# KNX_Relay_16CH_V0_2.net
KiCad netlist of a schematic drawn in Altium Designer
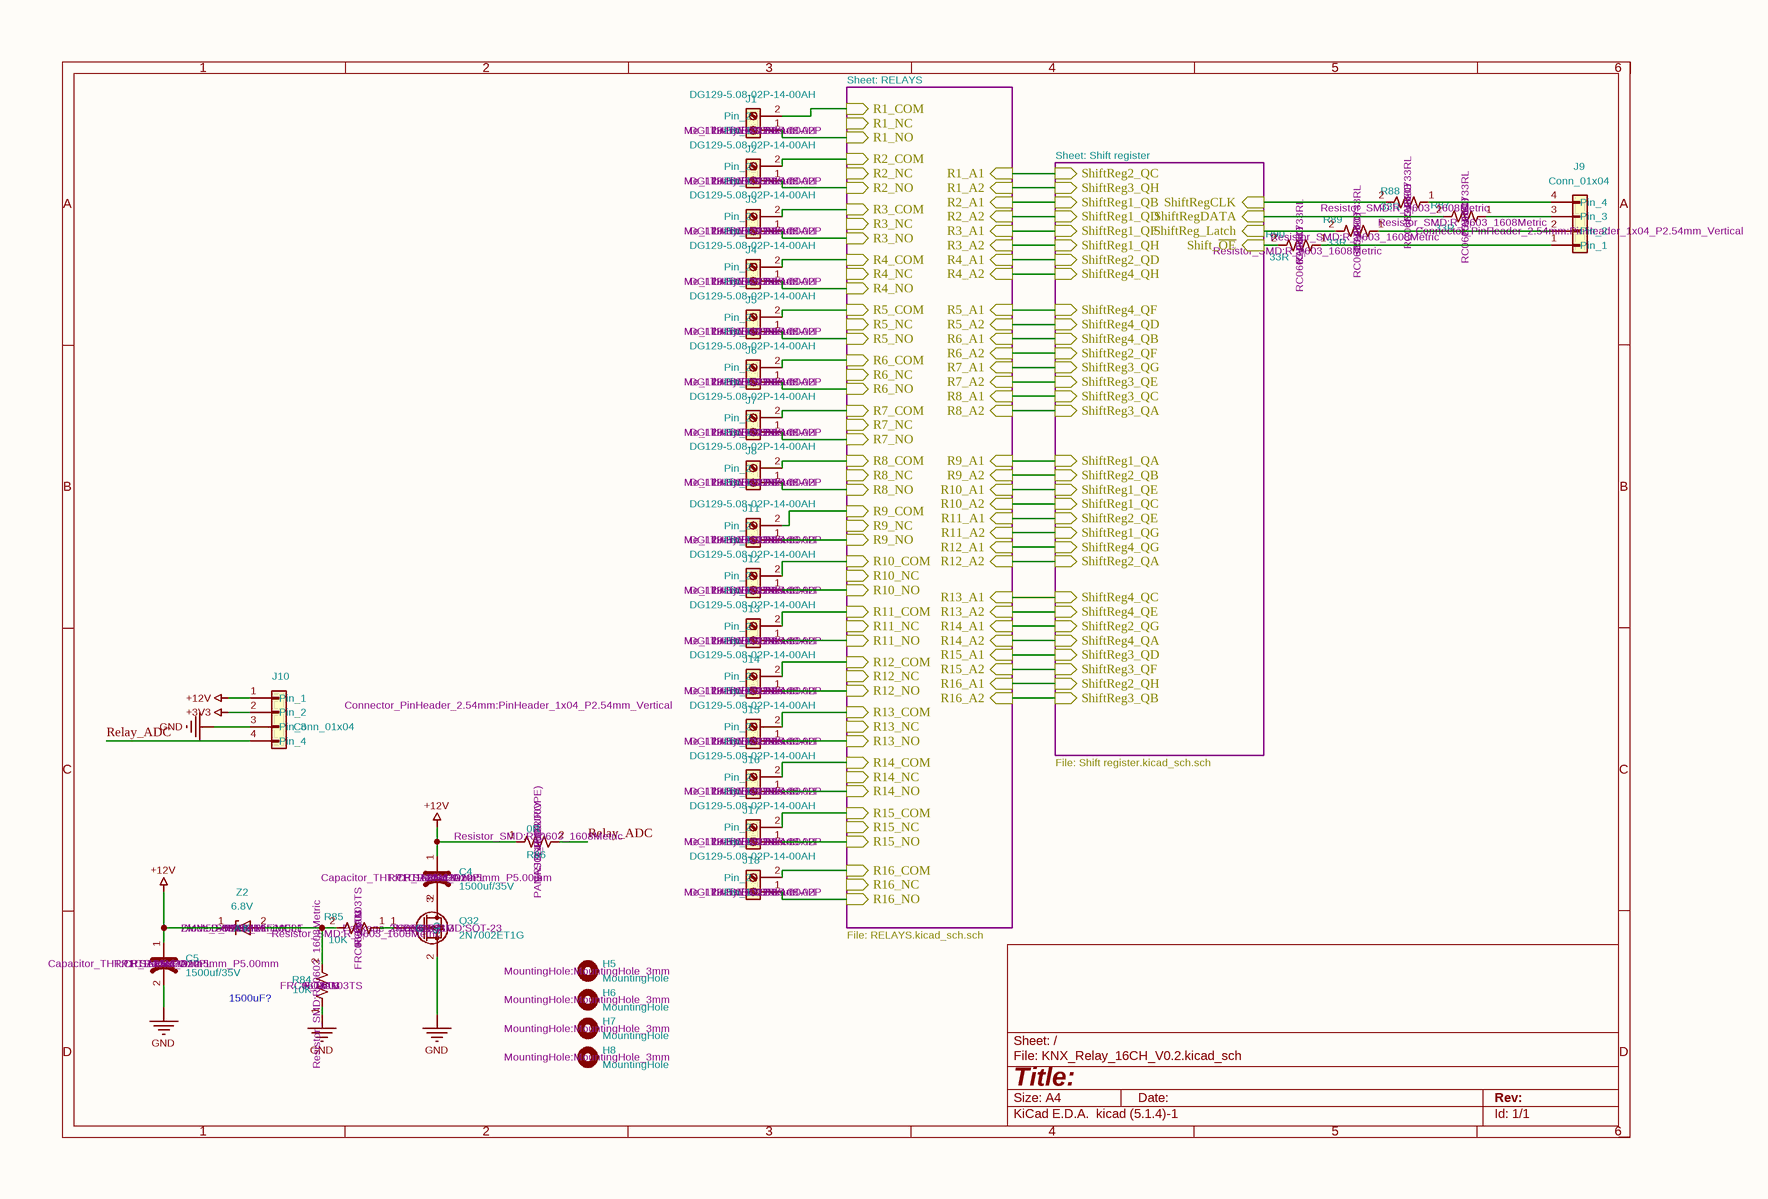
[diagram p0: KNX_Relay_16CH_V0.2.SchDoc]

(export (version "E")
  (design (tool "Eeschema 10.0.6"))
  (components
    (comp (ref "C4")
      (value "1500uf/35V")
      (footprint "Capacitor_THT:CP_Radial_D12.5mm_P5.00mm")
      (fields
        (field (name "MANUFACTURER PART NUMBER") "RP1C158M12020PL")
        (field (name "MANUFACTURER") "SAMWHA")
        (field (name "PACKAGE") "THT 12.5x20mm")
      )
      (libsource (lib "Device") (part "C_US"))
    )
    (comp (ref "C5")
      (value "1500uf/35V")
      (footprint "Capacitor_THT:CP_Radial_D12.5mm_P5.00mm")
      (fields
        (field (name "MANUFACTURER PART NUMBER") "RP1C158M12020PL")
        (field (name "MANUFACTURER") "SAMWHA")
        (field (name "PACKAGE") "THT 12.5x20mm")
      )
      (libsource (lib "Device") (part "C_US"))
    )
    (comp (ref "H5")
      (value "MountingHole")
      (footprint "MountingHole:MountingHole_3mm")
      (libsource (lib "Mechanical") (part "MountingHole"))
    )
    (comp (ref "H6")
      (value "MountingHole")
      (footprint "MountingHole:MountingHole_3mm")
      (libsource (lib "Mechanical") (part "MountingHole"))
    )
    (comp (ref "H7")
      (value "MountingHole")
      (footprint "MountingHole:MountingHole_3mm")
      (libsource (lib "Mechanical") (part "MountingHole"))
    )
    (comp (ref "H8")
      (value "MountingHole")
      (footprint "MountingHole:MountingHole_3mm")
      (libsource (lib "Mechanical") (part "MountingHole"))
    )
    (comp (ref "J1")
      (value "DG129-5.08-02P-14-00AH")
      (footprint "Me_Library:DG129-5.08-02P")
      (fields
        (field (name "MANUFACTURER PART NUMBER") "DG129-5.08-02P-14-00AH")
        (field (name "MANUFACTURER") "DEGSON")
        (field (name "PACKAGE") "THT V/T  5.08mm")
      )
      (libsource (lib "Connector") (part "Screw_Terminal_01x02"))
    )
    (comp (ref "J2")
      (value "DG129-5.08-02P-14-00AH")
      (footprint "Me_Library:DG129-5.08-02P")
      (fields
        (field (name "MANUFACTURER PART NUMBER") "DG129-5.08-02P-14-00AH")
        (field (name "MANUFACTURER") "DEGSON")
        (field (name "PACKAGE") "THT V/T  5.08mm")
      )
      (libsource (lib "Connector") (part "Screw_Terminal_01x02"))
    )
    (comp (ref "J3")
      (value "DG129-5.08-02P-14-00AH")
      (footprint "Me_Library:DG129-5.08-02P")
      (fields
        (field (name "MANUFACTURER PART NUMBER") "DG129-5.08-02P-14-00AH")
        (field (name "MANUFACTURER") "DEGSON")
        (field (name "PACKAGE") "THT V/T  5.08mm")
      )
      (libsource (lib "Connector") (part "Screw_Terminal_01x02"))
    )
    (comp (ref "J4")
      (value "DG129-5.08-02P-14-00AH")
      (footprint "Me_Library:DG129-5.08-02P")
      (fields
        (field (name "MANUFACTURER PART NUMBER") "DG129-5.08-02P-14-00AH")
        (field (name "MANUFACTURER") "DEGSON")
        (field (name "PACKAGE") "THT V/T  5.08mm")
      )
      (libsource (lib "Connector") (part "Screw_Terminal_01x02"))
    )
    (comp (ref "J5")
      (value "DG129-5.08-02P-14-00AH")
      (footprint "Me_Library:DG129-5.08-02P")
      (fields
        (field (name "MANUFACTURER PART NUMBER") "DG129-5.08-02P-14-00AH")
        (field (name "MANUFACTURER") "DEGSON")
        (field (name "PACKAGE") "THT V/T  5.08mm")
      )
      (libsource (lib "Connector") (part "Screw_Terminal_01x02"))
    )
    (comp (ref "J6")
      (value "DG129-5.08-02P-14-00AH")
      (footprint "Me_Library:DG129-5.08-02P")
      (fields
        (field (name "MANUFACTURER PART NUMBER") "DG129-5.08-02P-14-00AH")
        (field (name "MANUFACTURER") "DEGSON")
        (field (name "PACKAGE") "THT V/T  5.08mm")
      )
      (libsource (lib "Connector") (part "Screw_Terminal_01x02"))
    )
    (comp (ref "J7")
      (value "DG129-5.08-02P-14-00AH")
      (footprint "Me_Library:DG129-5.08-02P")
      (fields
        (field (name "MANUFACTURER PART NUMBER") "DG129-5.08-02P-14-00AH")
        (field (name "MANUFACTURER") "DEGSON")
        (field (name "PACKAGE") "THT V/T  5.08mm")
      )
      (libsource (lib "Connector") (part "Screw_Terminal_01x02"))
    )
    (comp (ref "J8")
      (value "DG129-5.08-02P-14-00AH")
      (footprint "Me_Library:DG129-5.08-02P")
      (fields
        (field (name "MANUFACTURER PART NUMBER") "DG129-5.08-02P-14-00AH")
        (field (name "MANUFACTURER") "DEGSON")
        (field (name "PACKAGE") "THT V/T  5.08mm")
      )
      (libsource (lib "Connector") (part "Screw_Terminal_01x02"))
    )
    (comp (ref "J9")
      (value "Conn_01x04")
      (footprint "Connector_PinHeader_2.54mm:PinHeader_1x04_P2.54mm_Vertical")
      (description "FEMALE HEADER 4PIN(1x4) 2.54mm THT V/T TRAY")
      (fields
        (field (name "MANUFACTURER PART NUMBER") "5PS1SDA85-104G0NNNAL-00")
        (field (name "MANUFACTURER") "AMTEK")
      )
      (libsource (lib "Connector_Generic") (part "Conn_01x04"))
    )
    (comp (ref "J10")
      (value "Conn_01x04")
      (footprint "Connector_PinHeader_2.54mm:PinHeader_1x04_P2.54mm_Vertical")
      (description "FEMALE HEADER 4PIN(1x4) 2.54mm THT V/T TRAY")
      (fields
        (field (name "MANUFACTURER PART NUMBER") "5PS1SDA85-104G0NNNAL-00")
        (field (name "MANUFACTURER") "AMTEK")
      )
      (libsource (lib "") (part "Conn_01x04_1"))
    )
    (comp (ref "J11")
      (value "DG129-5.08-02P-14-00AH")
      (footprint "Me_Library:DG129-5.08-02P")
      (fields
        (field (name "MANUFACTURER PART NUMBER") "DG129-5.08-02P-14-00AH")
        (field (name "MANUFACTURER") "DEGSON")
        (field (name "PACKAGE") "THT V/T  5.08mm")
      )
      (libsource (lib "Connector") (part "Screw_Terminal_01x02"))
    )
    (comp (ref "J12")
      (value "DG129-5.08-02P-14-00AH")
      (footprint "Me_Library:DG129-5.08-02P")
      (fields
        (field (name "MANUFACTURER PART NUMBER") "DG129-5.08-02P-14-00AH")
        (field (name "MANUFACTURER") "DEGSON")
        (field (name "PACKAGE") "THT V/T  5.08mm")
      )
      (libsource (lib "Connector") (part "Screw_Terminal_01x02"))
    )
    (comp (ref "J13")
      (value "DG129-5.08-02P-14-00AH")
      (footprint "Me_Library:DG129-5.08-02P")
      (fields
        (field (name "MANUFACTURER PART NUMBER") "DG129-5.08-02P-14-00AH")
        (field (name "MANUFACTURER") "DEGSON")
        (field (name "PACKAGE") "THT V/T  5.08mm")
      )
      (libsource (lib "Connector") (part "Screw_Terminal_01x02"))
    )
    (comp (ref "J14")
      (value "DG129-5.08-02P-14-00AH")
      (footprint "Me_Library:DG129-5.08-02P")
      (fields
        (field (name "MANUFACTURER PART NUMBER") "DG129-5.08-02P-14-00AH")
        (field (name "MANUFACTURER") "DEGSON")
        (field (name "PACKAGE") "THT V/T  5.08mm")
      )
      (libsource (lib "Connector") (part "Screw_Terminal_01x02"))
    )
    (comp (ref "J15")
      (value "DG129-5.08-02P-14-00AH")
      (footprint "Me_Library:DG129-5.08-02P")
      (fields
        (field (name "MANUFACTURER PART NUMBER") "DG129-5.08-02P-14-00AH")
        (field (name "MANUFACTURER") "DEGSON")
        (field (name "PACKAGE") "THT V/T  5.08mm")
      )
      (libsource (lib "Connector") (part "Screw_Terminal_01x02"))
    )
    (comp (ref "J16")
      (value "DG129-5.08-02P-14-00AH")
      (footprint "Me_Library:DG129-5.08-02P")
      (fields
        (field (name "MANUFACTURER PART NUMBER") "DG129-5.08-02P-14-00AH")
        (field (name "MANUFACTURER") "DEGSON")
        (field (name "PACKAGE") "THT V/T  5.08mm")
      )
      (libsource (lib "Connector") (part "Screw_Terminal_01x02"))
    )
    (comp (ref "J17")
      (value "DG129-5.08-02P-14-00AH")
      (footprint "Me_Library:DG129-5.08-02P")
      (fields
        (field (name "MANUFACTURER PART NUMBER") "DG129-5.08-02P-14-00AH")
        (field (name "MANUFACTURER") "DEGSON")
        (field (name "PACKAGE") "THT V/T  5.08mm")
      )
      (libsource (lib "Connector") (part "Screw_Terminal_01x02"))
    )
    (comp (ref "J18")
      (value "DG129-5.08-02P-14-00AH")
      (footprint "Me_Library:DG129-5.08-02P")
      (fields
        (field (name "MANUFACTURER PART NUMBER") "DG129-5.08-02P-14-00AH")
        (field (name "MANUFACTURER") "DEGSON")
        (field (name "PACKAGE") "THT V/T  5.08mm")
      )
      (libsource (lib "Connector") (part "Screw_Terminal_01x02"))
    )
    (comp (ref "Q32")
      (value "2N7002ET1G")
      (footprint "Package_TO_SOT_SMD:SOT-23")
      (fields
        (field (name "MANUFACTURER PART NUMBER") "2N7002ET1G")
        (field (name "MANUFACTURER") "onsemi")
        (field (name "PACKAGE") "SOT-23")
      )
      (libsource (lib "Transistor_FET_Other") (part "Q_NMOS_Depletion_GSD"))
    )
    (comp (ref "R84")
      (value "10K")
      (footprint "Resistor_SMD:R_0603_1608Metric")
      (fields
        (field (name "MANUFACTURER PART NUMBER") "FRC0603J103TS")
        (field (name "MANUFACTURER") "FOJAN")
        (field (name "PACKAGE") "R_0603")
      )
      (libsource (lib "Device") (part "R_US"))
    )
    (comp (ref "R85")
      (value "10K")
      (footprint "Resistor_SMD:R_0603_1608Metric")
      (fields
        (field (name "MANUFACTURER PART NUMBER") "FRC0603J103TS")
        (field (name "MANUFACTURER") "FOJAN")
        (field (name "PACKAGE") "R_0603")
      )
      (libsource (lib "Device") (part "R_US"))
    )
    (comp (ref "R86")
      (value "0R")
      (footprint "Resistor_SMD:R_0603_1608Metric")
      (description "RES.(1608) 0603 0 Ohms 1/10W JUMPER")
      (fields
        (field (name "MANUFACTURER PART NUMBER") "ERJ3GEY0R00V")
        (field (name "MANUFACTURER") "PANASONIC(EUROPE)")
        (field (name "PACKAGE") "R_0603")
        (field (name "Comment") "ERJ3GEY0R00V")
      )
      (libsource (lib "Device") (part "R_US"))
    )
    (comp (ref "R87")
      (value "33R")
      (footprint "Resistor_SMD:R_0603_1608Metric")
      (fields
        (field (name "MANUFACTURER PART NUMBER") "RC0603JR-0733RL")
        (field (name "MANUFACTURER") "YAGEO")
        (field (name "PACKAGE") "R_0603")
      )
      (libsource (lib "Device") (part "R_US"))
    )
    (comp (ref "R88")
      (value "33R")
      (footprint "Resistor_SMD:R_0603_1608Metric")
      (fields
        (field (name "MANUFACTURER PART NUMBER") "RC0603JR-0733RL")
        (field (name "MANUFACTURER") "YAGEO")
        (field (name "PACKAGE") "R_0603")
      )
      (libsource (lib "Device") (part "R_US"))
    )
    (comp (ref "R89")
      (value "33R")
      (footprint "Resistor_SMD:R_0603_1608Metric")
      (fields
        (field (name "MANUFACTURER PART NUMBER") "RC0603JR-0733RL")
        (field (name "MANUFACTURER") "YAGEO")
        (field (name "PACKAGE") "R_0603")
      )
      (libsource (lib "Device") (part "R_US"))
    )
    (comp (ref "R90")
      (value "33R")
      (footprint "Resistor_SMD:R_0603_1608Metric")
      (fields
        (field (name "MANUFACTURER PART NUMBER") "RC0603JR-0733RL")
        (field (name "MANUFACTURER") "YAGEO")
        (field (name "PACKAGE") "R_0603")
      )
      (libsource (lib "Device") (part "R_US"))
    )
    (comp (ref "Z2")
      (value "6.8V")
      (footprint "Diode_SMD:D_MiniMELF")
      (fields
        (field (name "MANUFACTURER") "PANJIT")
        (field (name "MANUFACTURER PART NUMBER") "ZMM55-C6V8_R1_10001")
        (field (name "PACKAGE") "D_MiniMELF")
      )
      (libsource (lib "Device") (part "D_Zener"))
    )
  )
  (nets
    (net (code "1") (name "+3V3") (class "Default")
      (node (ref "J10") (pin "2") (pinfunction "Pin_2_2") (pintype "passive"))
    )
    (net (code "2") (name "+12V") (class "Default")
      (node (ref "C4") (pin "1") (pinfunction "1_1") (pintype "passive"))
      (node (ref "C5") (pin "1") (pinfunction "1_1") (pintype "passive"))
      (node (ref "J10") (pin "1") (pinfunction "Pin_1_1") (pintype "passive"))
      (node (ref "R86") (pin "1") (pinfunction "1_1") (pintype "passive"))
      (node (ref "Z2") (pin "1") (pinfunction "K_1") (pintype "passive"))
    )
    (net (code "5") (name "/R1_COM") (class "Default")
      (node (ref "J1") (pin "2") (pinfunction "Pin_2_2") (pintype "passive"))
    )
    (net (code "7") (name "/R1_NO") (class "Default")
      (node (ref "J1") (pin "1") (pinfunction "Pin_1_1") (pintype "passive"))
    )
    (net (code "10") (name "/R2_COM") (class "Default")
      (node (ref "J2") (pin "2") (pinfunction "Pin_2_2") (pintype "passive"))
    )
    (net (code "12") (name "/R2_NO") (class "Default")
      (node (ref "J2") (pin "1") (pinfunction "Pin_1_1") (pintype "passive"))
    )
    (net (code "15") (name "/R3_COM") (class "Default")
      (node (ref "J3") (pin "2") (pinfunction "Pin_2_2") (pintype "passive"))
    )
    (net (code "17") (name "/R3_NO") (class "Default")
      (node (ref "J3") (pin "1") (pinfunction "Pin_1_1") (pintype "passive"))
    )
    (net (code "20") (name "/R4_COM") (class "Default")
      (node (ref "J4") (pin "2") (pinfunction "Pin_2_2") (pintype "passive"))
    )
    (net (code "22") (name "/R4_NO") (class "Default")
      (node (ref "J4") (pin "1") (pinfunction "Pin_1_1") (pintype "passive"))
    )
    (net (code "25") (name "/R5_COM") (class "Default")
      (node (ref "J5") (pin "2") (pinfunction "Pin_2_2") (pintype "passive"))
    )
    (net (code "27") (name "/R5_NO") (class "Default")
      (node (ref "J5") (pin "1") (pinfunction "Pin_1_1") (pintype "passive"))
    )
    (net (code "30") (name "/R6_COM") (class "Default")
      (node (ref "J6") (pin "2") (pinfunction "Pin_2_2") (pintype "passive"))
    )
    (net (code "32") (name "/R6_NO") (class "Default")
      (node (ref "J6") (pin "1") (pinfunction "Pin_1_1") (pintype "passive"))
    )
    (net (code "35") (name "/R7_COM") (class "Default")
      (node (ref "J7") (pin "2") (pinfunction "Pin_2_2") (pintype "passive"))
    )
    (net (code "37") (name "/R7_NO") (class "Default")
      (node (ref "J7") (pin "1") (pinfunction "Pin_1_1") (pintype "passive"))
    )
    (net (code "40") (name "/R8_COM") (class "Default")
      (node (ref "J8") (pin "2") (pinfunction "Pin_2_2") (pintype "passive"))
    )
    (net (code "42") (name "/R8_NO") (class "Default")
      (node (ref "J8") (pin "1") (pinfunction "Pin_1_1") (pintype "passive"))
    )
    (net (code "45") (name "/R9_COM") (class "Default")
      (node (ref "J11") (pin "2") (pinfunction "Pin_2_2") (pintype "passive"))
    )
    (net (code "47") (name "/R9_NO") (class "Default")
      (node (ref "J11") (pin "1") (pinfunction "Pin_1_1") (pintype "passive"))
    )
    (net (code "50") (name "/R10_COM") (class "Default")
      (node (ref "J12") (pin "2") (pinfunction "Pin_2_2") (pintype "passive"))
    )
    (net (code "52") (name "/R10_NO") (class "Default")
      (node (ref "J12") (pin "1") (pinfunction "Pin_1_1") (pintype "passive"))
    )
    (net (code "55") (name "/R11_COM") (class "Default")
      (node (ref "J13") (pin "2") (pinfunction "Pin_2_2") (pintype "passive"))
    )
    (net (code "57") (name "/R11_NO") (class "Default")
      (node (ref "J13") (pin "1") (pinfunction "Pin_1_1") (pintype "passive"))
    )
    (net (code "60") (name "/R12_COM") (class "Default")
      (node (ref "J14") (pin "2") (pinfunction "Pin_2_2") (pintype "passive"))
    )
    (net (code "62") (name "/R12_NO") (class "Default")
      (node (ref "J14") (pin "1") (pinfunction "Pin_1_1") (pintype "passive"))
    )
    (net (code "65") (name "/R13_COM") (class "Default")
      (node (ref "J15") (pin "2") (pinfunction "Pin_2_2") (pintype "passive"))
    )
    (net (code "67") (name "/R13_NO") (class "Default")
      (node (ref "J15") (pin "1") (pinfunction "Pin_1_1") (pintype "passive"))
    )
    (net (code "70") (name "/R14_COM") (class "Default")
      (node (ref "J16") (pin "2") (pinfunction "Pin_2_2") (pintype "passive"))
    )
    (net (code "72") (name "/R14_NO") (class "Default")
      (node (ref "J16") (pin "1") (pinfunction "Pin_1_1") (pintype "passive"))
    )
    (net (code "75") (name "/R15_COM") (class "Default")
      (node (ref "J17") (pin "2") (pinfunction "Pin_2_2") (pintype "passive"))
    )
    (net (code "77") (name "/R15_NO") (class "Default")
      (node (ref "J17") (pin "1") (pinfunction "Pin_1_1") (pintype "passive"))
    )
    (net (code "80") (name "/R16_COM") (class "Default")
      (node (ref "J18") (pin "2") (pinfunction "Pin_2_2") (pintype "passive"))
    )
    (net (code "82") (name "/R16_NO") (class "Default")
      (node (ref "J18") (pin "1") (pinfunction "Pin_1_1") (pintype "passive"))
    )
    (net (code "83") (name "/Relay_ADC") (class "Default")
      (node (ref "J10") (pin "4") (pinfunction "Pin_4_4") (pintype "passive"))
      (node (ref "R86") (pin "2") (pinfunction "2_2") (pintype "passive"))
    )
    (net (code "84") (name "/ShiftRegCLK") (class "Default")
      (node (ref "R88") (pin "2") (pinfunction "2_2") (pintype "passive"))
    )
    (net (code "85") (name "/ShiftRegDATA") (class "Default")
      (node (ref "R87") (pin "2") (pinfunction "2_2") (pintype "passive"))
    )
    (net (code "86") (name "/ShiftReg_Latch") (class "Default")
      (node (ref "R89") (pin "2") (pinfunction "2_2") (pintype "passive"))
    )
    (net (code "87") (name "/Shift_~{OE}") (class "Default")
      (node (ref "R90") (pin "2") (pinfunction "2_2") (pintype "passive"))
    )
    (net (code "88") (name "GND") (class "Default")
      (node (ref "C5") (pin "2") (pinfunction "2_2") (pintype "passive"))
      (node (ref "J10") (pin "3") (pinfunction "Pin_3_3") (pintype "passive"))
      (node (ref "Q32") (pin "2") (pinfunction "S_2") (pintype "passive"))
      (node (ref "R84") (pin "1") (pinfunction "1_1") (pintype "passive"))
    )
    (net (code "89") (name "Net-(J9-Pin_1)") (class "Default")
      (node (ref "J9") (pin "1") (pinfunction "Pin_1_1") (pintype "passive"))
      (node (ref "R90") (pin "1") (pinfunction "1_1") (pintype "passive"))
    )
    (net (code "90") (name "Net-(J9-Pin_2)") (class "Default")
      (node (ref "J9") (pin "2") (pinfunction "Pin_2_2") (pintype "passive"))
      (node (ref "R89") (pin "1") (pinfunction "1_1") (pintype "passive"))
    )
    (net (code "91") (name "Net-(J9-Pin_3)") (class "Default")
      (node (ref "J9") (pin "3") (pinfunction "Pin_3_3") (pintype "passive"))
      (node (ref "R87") (pin "1") (pinfunction "1_1") (pintype "passive"))
    )
    (net (code "92") (name "Net-(J9-Pin_4)") (class "Default")
      (node (ref "J9") (pin "4") (pinfunction "Pin_4_4") (pintype "passive"))
      (node (ref "R88") (pin "1") (pinfunction "1_1") (pintype "passive"))
    )
    (net (code "93") (name "Net-(Q32-D)") (class "Default")
      (node (ref "C4") (pin "2") (pinfunction "2_2") (pintype "passive"))
      (node (ref "Q32") (pin "3") (pinfunction "D_3") (pintype "passive"))
    )
    (net (code "94") (name "Net-(Q32-G)") (class "Default")
      (node (ref "Q32") (pin "1") (pinfunction "G_1") (pintype "passive"))
      (node (ref "R85") (pin "1") (pinfunction "1_1") (pintype "passive"))
    )
    (net (code "95") (name "Net-(Z2-A)") (class "Default")
      (node (ref "R84") (pin "2") (pinfunction "2_2") (pintype "passive"))
      (node (ref "R85") (pin "2") (pinfunction "2_2") (pintype "passive"))
      (node (ref "Z2") (pin "2") (pinfunction "A_2") (pintype "passive"))
    )
  )
)
